# STRWL-S04-V00-Microcontroller.net
KiCad netlist of a schematic drawn in Altium Designer
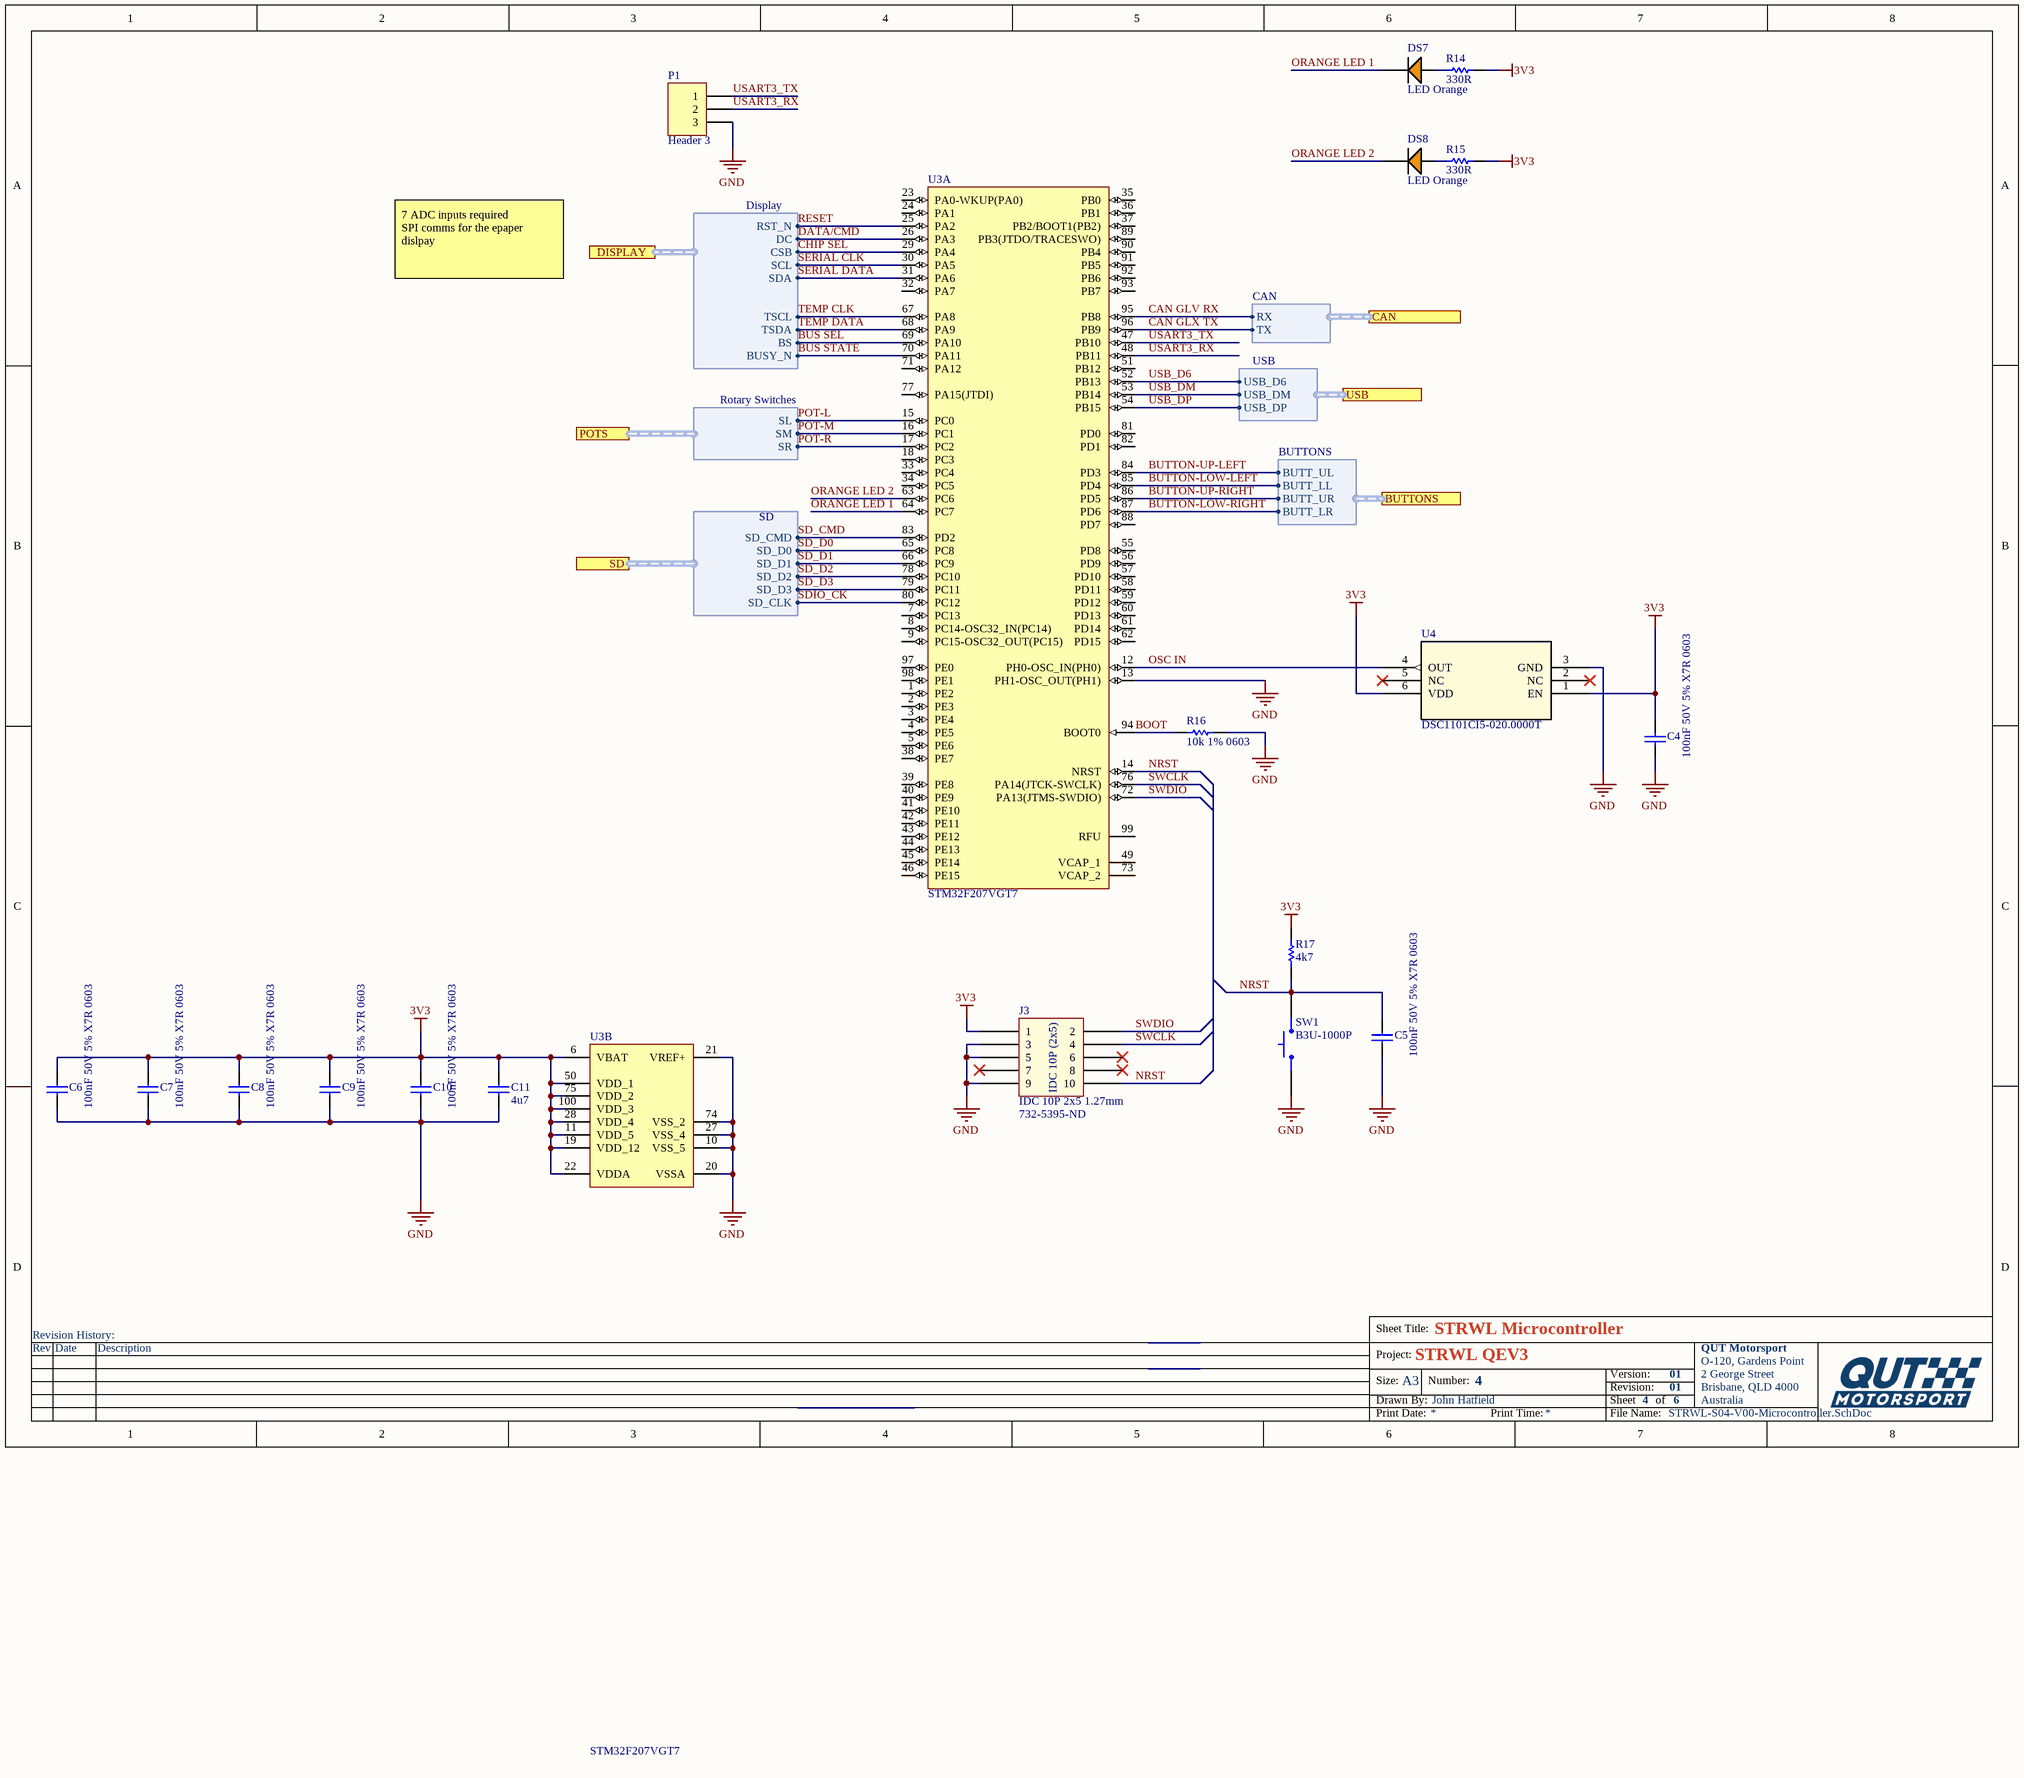
[diagram p0: STRWL-S04-V00-Microcontroller.SchDoc]

(export (version "E")
  (design (tool "Eeschema 10.0.6"))
  (components
    (comp (ref "C4")
      (value "100nF 50V 5% X7R 0603")
      (footprint "Cap_Ceramic_0603")
      (description "Capacitor, Ceramic, SMD, 100nF, 50V, 5%, X7R, 0603")
      (libsource (lib "StandardCapacitors") (part "100nF 50V 5% X7R 0603"))
    )
    (comp (ref "C5")
      (value "100nF 50V 5% X7R 0603")
      (footprint "Cap_Ceramic_0603")
      (description "Capacitor, Ceramic, SMD, 100nF, 50V, 5%, X7R, 0603")
      (libsource (lib "StandardCapacitors") (part "100nF 50V 5% X7R 0603"))
    )
    (comp (ref "C6")
      (value "100nF 50V 5% X7R 0603")
      (footprint "Cap_Ceramic_0603")
      (description "Capacitor, Ceramic, SMD, 100nF, 50V, 5%, X7R, 0603")
      (libsource (lib "StandardCapacitors") (part "100nF 50V 5% X7R 0603"))
    )
    (comp (ref "C7")
      (value "100nF 50V 5% X7R 0603")
      (footprint "Cap_Ceramic_0603")
      (description "Capacitor, Ceramic, SMD, 100nF, 50V, 5%, X7R, 0603")
      (libsource (lib "StandardCapacitors") (part "100nF 50V 5% X7R 0603"))
    )
    (comp (ref "C8")
      (value "100nF 50V 5% X7R 0603")
      (footprint "Cap_Ceramic_0603")
      (description "Capacitor, Ceramic, SMD, 100nF, 50V, 5%, X7R, 0603")
      (libsource (lib "StandardCapacitors") (part "100nF 50V 5% X7R 0603"))
    )
    (comp (ref "C9")
      (value "100nF 50V 5% X7R 0603")
      (footprint "Cap_Ceramic_0603")
      (description "Capacitor, Ceramic, SMD, 100nF, 50V, 5%, X7R, 0603")
      (libsource (lib "StandardCapacitors") (part "100nF 50V 5% X7R 0603"))
    )
    (comp (ref "C10")
      (value "100nF 50V 5% X7R 0603")
      (footprint "Cap_Ceramic_0603")
      (description "Capacitor, Ceramic, SMD, 100nF, 50V, 5%, X7R, 0603")
      (libsource (lib "StandardCapacitors") (part "100nF 50V 5% X7R 0603"))
    )
    (comp (ref "C11")
      (value "4u7")
      (footprint "Cap_Ceramic_0603")
      (description "Capacitor, Ceramic, SMD, 4u7, 50V, 5%, X7R, 0603")
      (libsource (lib "StandardCapacitors") (part "4u7 50V 5% X7R 0603"))
    )
    (comp (ref "DS7")
      (value "LED Orange")
      (footprint "LED ORANGE 0603")
      (libsource (lib "QUTMS_LEDLibrary") (part "LED ORANGE 0603"))
    )
    (comp (ref "DS8")
      (value "LED Orange")
      (footprint "LED ORANGE 0603")
      (libsource (lib "QUTMS_LEDLibrary") (part "LED ORANGE 0603"))
    )
    (comp (ref "J3")
      (value "IDC 10P 2x5 1.27mm")
      (footprint "IDC 1.27MM 10P")
      (libsource (lib "IDCConnectors") (part "IDC 10P 2x5 1.27mm"))
    )
    (comp (ref "P1")
      (value "Header 3")
      (footprint "HDR1X3")
      (description "Header, 3-Pin")
      (fields (field (name "PUBLISHER") "Altium Limited"))
      (libsource (lib "Miscellaneous Connectors") (part "Header 3"))
    )
    (comp (ref "R14")
      (value "330R")
      (footprint "Res_ThinFilm_0603")
      (description "Resistor, SMD, 330R, 0.1W, 5%, 0603")
      (libsource (lib "StandardResistors") (part "330R 5% 0603"))
    )
    (comp (ref "R15")
      (value "330R")
      (footprint "Res_ThinFilm_0603")
      (description "Resistor, SMD, 330R, 0.1W, 5%, 0603")
      (libsource (lib "StandardResistors") (part "330R 5% 0603"))
    )
    (comp (ref "R16")
      (value "10k 1% 0603")
      (footprint "Res_ThinFilm_0603")
      (description "Resistor, SMD, 20k, 0.1W, 5%, 0603")
      (libsource (lib "QUTMS-MCISOLibrary") (part "20k 1% 0603"))
    )
    (comp (ref "R17")
      (value "4k7")
      (footprint "Res_ThinFilm_0603")
      (description "Resistor, SMD, 4k7, 0.1W, 5%, 0603")
      (libsource (lib "StandardResistors") (part "4k7 5% 0603"))
    )
    (comp (ref "SW1")
      (value "B3U-1000P")
      (footprint "BTN B3U-1000P")
      (description "Omron B3U-1000P Ultra Miniture Switch")
      (libsource (lib "QUTMS_SwitchLibrary") (part "BTN B3U-1000P"))
    )
    (comp (ref "U3")
      (value "STM32F207VGT7")
      (footprint "STM-LQFP100_N")
      (libsource (lib "STM32F207VGT7") (part "STM32F207VGT7-Custom"))
    )
    (comp (ref "U4")
      (value "DSC1101CI5-020.0000T")
      (footprint "VDFN6_3P2X2P5_MCH")
      (description "No Description Available")
      (fields (field (name "COPYRIGHT") "Copyright (C) 2018 Accelerated Designs. All rights reserved"))
      (libsource (lib "DSC1101CI5-020.0000T") (part "DSC1101CI5-020.0000T"))
    )
  )
  (nets
    (net (code "8") (name "/BOOT") (class "Default")
      (node (ref "R16") (pin "1") (pinfunction "1_1") (pintype "passive"))
      (node (ref "U3") (pin "94") (pinfunction "BOOT0_94") (pintype "input"))
    )
    (net (code "9") (name "/BUS SEL") (class "Default")
      (node (ref "U3") (pin "69") (pinfunction "PA10_69") (pintype "bidirectional"))
    )
    (net (code "10") (name "/BUS STATE") (class "Default")
      (node (ref "U3") (pin "70") (pinfunction "PA11_70") (pintype "bidirectional"))
    )
    (net (code "11") (name "/BUTTON-LOW-LEFT") (class "Default")
      (node (ref "U3") (pin "85") (pinfunction "PD4_85") (pintype "bidirectional"))
    )
    (net (code "12") (name "/BUTTON-LOW-RIGHT") (class "Default")
      (node (ref "U3") (pin "87") (pinfunction "PD6_87") (pintype "bidirectional"))
    )
    (net (code "13") (name "/BUTTON-UP-LEFT") (class "Default")
      (node (ref "U3") (pin "84") (pinfunction "PD3_84") (pintype "bidirectional"))
    )
    (net (code "14") (name "/BUTTON-UP-RIGHT") (class "Default")
      (node (ref "U3") (pin "86") (pinfunction "PD5_86") (pintype "bidirectional"))
    )
    (net (code "15") (name "/CAN GLV RX") (class "Default")
      (node (ref "U3") (pin "95") (pinfunction "PB8_95") (pintype "bidirectional"))
    )
    (net (code "16") (name "/CAN GLX TX") (class "Default")
      (node (ref "U3") (pin "96") (pinfunction "PB9_96") (pintype "bidirectional"))
    )
    (net (code "17") (name "/CHIP SEL") (class "Default")
      (node (ref "U3") (pin "29") (pinfunction "PA4_29") (pintype "bidirectional"))
    )
    (net (code "18") (name "/DATA{slash}CMD") (class "Default")
      (node (ref "U3") (pin "26") (pinfunction "PA3_26") (pintype "bidirectional"))
    )
    (net (code "19") (name "/NRST") (class "Default")
      (node (ref "C5") (pin "2") (pinfunction "2_2") (pintype "passive"))
      (node (ref "J3") (pin "10") (pinfunction "10_10") (pintype "passive"))
      (node (ref "R17") (pin "1") (pinfunction "1_1") (pintype "passive"))
      (node (ref "SW1") (pin "2") (pinfunction "2_2") (pintype "passive"))
      (node (ref "U3") (pin "14") (pinfunction "NRST_14") (pintype "bidirectional"))
    )
    (net (code "20") (name "/ORANGE LED 1") (class "Default")
      (node (ref "DS7") (pin "2") (pinfunction "C_2") (pintype "passive"))
      (node (ref "U3") (pin "64") (pinfunction "PC7_64") (pintype "bidirectional"))
    )
    (net (code "21") (name "/ORANGE LED 2") (class "Default")
      (node (ref "DS8") (pin "2") (pinfunction "C_2") (pintype "passive"))
      (node (ref "U3") (pin "63") (pinfunction "PC6_63") (pintype "bidirectional"))
    )
    (net (code "22") (name "/OSC IN") (class "Default")
      (node (ref "U3") (pin "12") (pinfunction "PH0-OSC_IN(PH0)_12") (pintype "bidirectional"))
      (node (ref "U4") (pin "4") (pinfunction "OUT_4") (pintype "output"))
    )
    (net (code "23") (name "/POT-L") (class "Default")
      (node (ref "U3") (pin "15") (pinfunction "PC0_15") (pintype "bidirectional"))
    )
    (net (code "24") (name "/POT-M") (class "Default")
      (node (ref "U3") (pin "16") (pinfunction "PC1_16") (pintype "bidirectional"))
    )
    (net (code "25") (name "/POT-R") (class "Default")
      (node (ref "U3") (pin "17") (pinfunction "PC2_17") (pintype "bidirectional"))
    )
    (net (code "26") (name "/RESET") (class "Default")
      (node (ref "U3") (pin "25") (pinfunction "PA2_25") (pintype "bidirectional"))
    )
    (net (code "27") (name "/SDIO_CK") (class "Default")
      (node (ref "U3") (pin "80") (pinfunction "PC12_80") (pintype "bidirectional"))
    )
    (net (code "28") (name "/SD_CMD") (class "Default")
      (node (ref "U3") (pin "83") (pinfunction "PD2_83") (pintype "bidirectional"))
    )
    (net (code "29") (name "/SD_D0") (class "Default")
      (node (ref "U3") (pin "65") (pinfunction "PC8_65") (pintype "bidirectional"))
    )
    (net (code "30") (name "/SD_D1") (class "Default")
      (node (ref "U3") (pin "66") (pinfunction "PC9_66") (pintype "bidirectional"))
    )
    (net (code "31") (name "/SD_D2") (class "Default")
      (node (ref "U3") (pin "78") (pinfunction "PC10_78") (pintype "bidirectional"))
    )
    (net (code "32") (name "/SD_D3") (class "Default")
      (node (ref "U3") (pin "79") (pinfunction "PC11_79") (pintype "bidirectional"))
    )
    (net (code "33") (name "/SERIAL CLK") (class "Default")
      (node (ref "U3") (pin "30") (pinfunction "PA5_30") (pintype "bidirectional"))
    )
    (net (code "34") (name "/SERIAL DATA") (class "Default")
      (node (ref "U3") (pin "31") (pinfunction "PA6_31") (pintype "bidirectional"))
    )
    (net (code "35") (name "/SWCLK") (class "Default")
      (node (ref "J3") (pin "4") (pinfunction "4_4") (pintype "passive"))
      (node (ref "U3") (pin "76") (pinfunction "PA14(JTCK-SWCLK)_76") (pintype "bidirectional"))
    )
    (net (code "36") (name "/SWDIO") (class "Default")
      (node (ref "J3") (pin "2") (pinfunction "2_2") (pintype "passive"))
      (node (ref "U3") (pin "72") (pinfunction "PA13(JTMS-SWDIO)_72") (pintype "bidirectional"))
    )
    (net (code "37") (name "/TEMP CLK") (class "Default")
      (node (ref "U3") (pin "67") (pinfunction "PA8_67") (pintype "bidirectional"))
    )
    (net (code "38") (name "/TEMP DATA") (class "Default")
      (node (ref "U3") (pin "68") (pinfunction "PA9_68") (pintype "bidirectional"))
    )
    (net (code "39") (name "/USART3_RX") (class "Default")
      (node (ref "P1") (pin "2") (pinfunction "2_2") (pintype "passive"))
      (node (ref "U3") (pin "48") (pinfunction "PB11_48") (pintype "bidirectional"))
    )
    (net (code "40") (name "/USART3_TX") (class "Default")
      (node (ref "P1") (pin "1") (pinfunction "1_1") (pintype "passive"))
      (node (ref "U3") (pin "47") (pinfunction "PB10_47") (pintype "bidirectional"))
    )
    (net (code "41") (name "/USB_D6") (class "Default")
      (node (ref "U3") (pin "52") (pinfunction "PB13_52") (pintype "bidirectional"))
    )
    (net (code "42") (name "/USB_DM") (class "Default")
      (node (ref "U3") (pin "53") (pinfunction "PB14_53") (pintype "bidirectional"))
    )
    (net (code "43") (name "/USB_DP") (class "Default")
      (node (ref "U3") (pin "54") (pinfunction "PB15_54") (pintype "bidirectional"))
    )
    (net (code "50") (name "3V3") (class "Default")
      (node (ref "C10") (pin "2") (pinfunction "2_2") (pintype "passive"))
      (node (ref "C11") (pin "2") (pinfunction "2_2") (pintype "passive"))
      (node (ref "C4") (pin "2") (pinfunction "2_2") (pintype "passive"))
      (node (ref "C6") (pin "2") (pinfunction "2_2") (pintype "passive"))
      (node (ref "C7") (pin "2") (pinfunction "2_2") (pintype "passive"))
      (node (ref "C8") (pin "2") (pinfunction "2_2") (pintype "passive"))
      (node (ref "C9") (pin "2") (pinfunction "2_2") (pintype "passive"))
      (node (ref "J3") (pin "1") (pinfunction "1_1") (pintype "passive"))
      (node (ref "R14") (pin "2") (pinfunction "2_2") (pintype "passive"))
      (node (ref "R15") (pin "2") (pinfunction "2_2") (pintype "passive"))
      (node (ref "R17") (pin "2") (pinfunction "2_2") (pintype "passive"))
      (node (ref "U3") (pin "100") (pinfunction "VDD_3_100") (pintype "power_in"))
      (node (ref "U3") (pin "11") (pinfunction "VDD_5_11") (pintype "power_in"))
      (node (ref "U3") (pin "19") (pinfunction "VDD_12_19") (pintype "power_in"))
      (node (ref "U3") (pin "22") (pinfunction "VDDA_22") (pintype "power_in"))
      (node (ref "U3") (pin "28") (pinfunction "VDD_4_28") (pintype "power_in"))
      (node (ref "U3") (pin "50") (pinfunction "VDD_1_50") (pintype "power_in"))
      (node (ref "U3") (pin "6") (pinfunction "VBAT_6") (pintype "power_in"))
      (node (ref "U3") (pin "75") (pinfunction "VDD_2_75") (pintype "power_in"))
      (node (ref "U4") (pin "1") (pinfunction "EN_1") (pintype "passive"))
      (node (ref "U4") (pin "6") (pinfunction "VDD_6") (pintype "power_in"))
    )
    (net (code "51") (name "GND") (class "Default")
      (node (ref "C10") (pin "1") (pinfunction "1_1") (pintype "passive"))
      (node (ref "C11") (pin "1") (pinfunction "1_1") (pintype "passive"))
      (node (ref "C4") (pin "1") (pinfunction "1_1") (pintype "passive"))
      (node (ref "C5") (pin "1") (pinfunction "1_1") (pintype "passive"))
      (node (ref "C6") (pin "1") (pinfunction "1_1") (pintype "passive"))
      (node (ref "C7") (pin "1") (pinfunction "1_1") (pintype "passive"))
      (node (ref "C8") (pin "1") (pinfunction "1_1") (pintype "passive"))
      (node (ref "C9") (pin "1") (pinfunction "1_1") (pintype "passive"))
      (node (ref "J3") (pin "3") (pinfunction "3_3") (pintype "passive"))
      (node (ref "J3") (pin "5") (pinfunction "5_5") (pintype "passive"))
      (node (ref "J3") (pin "9") (pinfunction "9_9") (pintype "passive"))
      (node (ref "P1") (pin "3") (pinfunction "3_3") (pintype "passive"))
      (node (ref "R16") (pin "2") (pinfunction "2_2") (pintype "passive"))
      (node (ref "SW1") (pin "1") (pinfunction "1_1") (pintype "passive"))
      (node (ref "U3") (pin "10") (pinfunction "VSS_5_10") (pintype "power_in"))
      (node (ref "U3") (pin "13") (pinfunction "PH1-OSC_OUT(PH1)_13") (pintype "bidirectional"))
      (node (ref "U3") (pin "20") (pinfunction "VSSA_20") (pintype "power_in"))
      (node (ref "U3") (pin "21") (pinfunction "VREF+_21") (pintype "power_in"))
      (node (ref "U3") (pin "27") (pinfunction "VSS_4_27") (pintype "power_in"))
      (node (ref "U3") (pin "74") (pinfunction "VSS_2_74") (pintype "power_in"))
      (node (ref "U4") (pin "3") (pinfunction "GND_3") (pintype "passive"))
    )
    (net (code "52") (name "Net-(DS7-A)") (class "Default")
      (node (ref "DS7") (pin "1") (pinfunction "A_1") (pintype "passive"))
      (node (ref "R14") (pin "1") (pinfunction "1_1") (pintype "passive"))
    )
    (net (code "53") (name "Net-(DS8-A)") (class "Default")
      (node (ref "DS8") (pin "1") (pinfunction "A_1") (pintype "passive"))
      (node (ref "R15") (pin "1") (pinfunction "1_1") (pintype "passive"))
    )
    (net (code "54") (name "unconnected-(J3-Pad6)") (class "Default")
      (node (ref "J3") (pin "6") (pinfunction "6_6") (pintype "passive+no_connect"))
    )
    (net (code "55") (name "unconnected-(J3-Pad7)") (class "Default")
      (node (ref "J3") (pin "7") (pinfunction "7_7") (pintype "passive+no_connect"))
    )
    (net (code "56") (name "unconnected-(J3-Pad8)") (class "Default")
      (node (ref "J3") (pin "8") (pinfunction "8_8") (pintype "passive+no_connect"))
    )
    (net (code "57") (name "unconnected-(U3A-PA0-WKUP(PA0)-Pad23)") (class "Default")
      (node (ref "U3") (pin "23") (pinfunction "PA0-WKUP(PA0)_23") (pintype "bidirectional"))
    )
    (net (code "58") (name "unconnected-(U3A-PA1-Pad24)") (class "Default")
      (node (ref "U3") (pin "24") (pinfunction "PA1_24") (pintype "bidirectional"))
    )
    (net (code "59") (name "unconnected-(U3A-PA7-Pad32)") (class "Default")
      (node (ref "U3") (pin "32") (pinfunction "PA7_32") (pintype "bidirectional"))
    )
    (net (code "60") (name "unconnected-(U3A-PA12-Pad71)") (class "Default")
      (node (ref "U3") (pin "71") (pinfunction "PA12_71") (pintype "bidirectional"))
    )
    (net (code "61") (name "unconnected-(U3A-PA15(JTDI)-Pad77)") (class "Default")
      (node (ref "U3") (pin "77") (pinfunction "PA15(JTDI)_77") (pintype "bidirectional"))
    )
    (net (code "62") (name "unconnected-(U3A-PB0-Pad35)") (class "Default")
      (node (ref "U3") (pin "35") (pinfunction "PB0_35") (pintype "bidirectional"))
    )
    (net (code "63") (name "unconnected-(U3A-PB1-Pad36)") (class "Default")
      (node (ref "U3") (pin "36") (pinfunction "PB1_36") (pintype "bidirectional"))
    )
    (net (code "64") (name "unconnected-(U3A-PB2{slash}BOOT1(PB2)-Pad37)") (class "Default")
      (node (ref "U3") (pin "37") (pinfunction "PB2/BOOT1(PB2)_37") (pintype "bidirectional"))
    )
    (net (code "65") (name "unconnected-(U3A-PB3(JTDO{slash}TRACESWO)-Pad89)") (class "Default")
      (node (ref "U3") (pin "89") (pinfunction "PB3(JTDO/TRACESWO)_89") (pintype "bidirectional"))
    )
    (net (code "66") (name "unconnected-(U3A-PB4-Pad90)") (class "Default")
      (node (ref "U3") (pin "90") (pinfunction "PB4_90") (pintype "bidirectional"))
    )
    (net (code "67") (name "unconnected-(U3A-PB5-Pad91)") (class "Default")
      (node (ref "U3") (pin "91") (pinfunction "PB5_91") (pintype "bidirectional"))
    )
    (net (code "68") (name "unconnected-(U3A-PB6-Pad92)") (class "Default")
      (node (ref "U3") (pin "92") (pinfunction "PB6_92") (pintype "bidirectional"))
    )
    (net (code "69") (name "unconnected-(U3A-PB7-Pad93)") (class "Default")
      (node (ref "U3") (pin "93") (pinfunction "PB7_93") (pintype "bidirectional"))
    )
    (net (code "70") (name "unconnected-(U3A-PB12-Pad51)") (class "Default")
      (node (ref "U3") (pin "51") (pinfunction "PB12_51") (pintype "bidirectional"))
    )
    (net (code "71") (name "unconnected-(U3A-PC3-Pad18)") (class "Default")
      (node (ref "U3") (pin "18") (pinfunction "PC3_18") (pintype "bidirectional"))
    )
    (net (code "72") (name "unconnected-(U3A-PC4-Pad33)") (class "Default")
      (node (ref "U3") (pin "33") (pinfunction "PC4_33") (pintype "bidirectional"))
    )
    (net (code "73") (name "unconnected-(U3A-PC5-Pad34)") (class "Default")
      (node (ref "U3") (pin "34") (pinfunction "PC5_34") (pintype "bidirectional"))
    )
    (net (code "74") (name "unconnected-(U3A-PC13-Pad7)") (class "Default")
      (node (ref "U3") (pin "7") (pinfunction "PC13_7") (pintype "bidirectional"))
    )
    (net (code "75") (name "unconnected-(U3A-PC14-OSC32_IN(PC14)-Pad8)") (class "Default")
      (node (ref "U3") (pin "8") (pinfunction "PC14-OSC32_IN(PC14)_8") (pintype "bidirectional"))
    )
    (net (code "76") (name "unconnected-(U3A-PC15-OSC32_OUT(PC15)-Pad9)") (class "Default")
      (node (ref "U3") (pin "9") (pinfunction "PC15-OSC32_OUT(PC15)_9") (pintype "bidirectional"))
    )
    (net (code "77") (name "unconnected-(U3A-PD0-Pad81)") (class "Default")
      (node (ref "U3") (pin "81") (pinfunction "PD0_81") (pintype "bidirectional"))
    )
    (net (code "78") (name "unconnected-(U3A-PD1-Pad82)") (class "Default")
      (node (ref "U3") (pin "82") (pinfunction "PD1_82") (pintype "bidirectional"))
    )
    (net (code "79") (name "unconnected-(U3A-PD7-Pad88)") (class "Default")
      (node (ref "U3") (pin "88") (pinfunction "PD7_88") (pintype "bidirectional"))
    )
    (net (code "80") (name "unconnected-(U3A-PD8-Pad55)") (class "Default")
      (node (ref "U3") (pin "55") (pinfunction "PD8_55") (pintype "bidirectional"))
    )
    (net (code "81") (name "unconnected-(U3A-PD9-Pad56)") (class "Default")
      (node (ref "U3") (pin "56") (pinfunction "PD9_56") (pintype "bidirectional"))
    )
    (net (code "82") (name "unconnected-(U3A-PD10-Pad57)") (class "Default")
      (node (ref "U3") (pin "57") (pinfunction "PD10_57") (pintype "bidirectional"))
    )
    (net (code "83") (name "unconnected-(U3A-PD11-Pad58)") (class "Default")
      (node (ref "U3") (pin "58") (pinfunction "PD11_58") (pintype "bidirectional"))
    )
    (net (code "84") (name "unconnected-(U3A-PD12-Pad59)") (class "Default")
      (node (ref "U3") (pin "59") (pinfunction "PD12_59") (pintype "bidirectional"))
    )
    (net (code "85") (name "unconnected-(U3A-PD13-Pad60)") (class "Default")
      (node (ref "U3") (pin "60") (pinfunction "PD13_60") (pintype "bidirectional"))
    )
    (net (code "86") (name "unconnected-(U3A-PD14-Pad61)") (class "Default")
      (node (ref "U3") (pin "61") (pinfunction "PD14_61") (pintype "bidirectional"))
    )
    (net (code "87") (name "unconnected-(U3A-PD15-Pad62)") (class "Default")
      (node (ref "U3") (pin "62") (pinfunction "PD15_62") (pintype "bidirectional"))
    )
    (net (code "88") (name "unconnected-(U3A-PE0-Pad97)") (class "Default")
      (node (ref "U3") (pin "97") (pinfunction "PE0_97") (pintype "bidirectional"))
    )
    (net (code "89") (name "unconnected-(U3A-PE1-Pad98)") (class "Default")
      (node (ref "U3") (pin "98") (pinfunction "PE1_98") (pintype "bidirectional"))
    )
    (net (code "90") (name "unconnected-(U3A-PE2-Pad1)") (class "Default")
      (node (ref "U3") (pin "1") (pinfunction "PE2_1") (pintype "bidirectional"))
    )
    (net (code "91") (name "unconnected-(U3A-PE3-Pad2)") (class "Default")
      (node (ref "U3") (pin "2") (pinfunction "PE3_2") (pintype "bidirectional"))
    )
    (net (code "92") (name "unconnected-(U3A-PE4-Pad3)") (class "Default")
      (node (ref "U3") (pin "3") (pinfunction "PE4_3") (pintype "bidirectional"))
    )
    (net (code "93") (name "unconnected-(U3A-PE5-Pad4)") (class "Default")
      (node (ref "U3") (pin "4") (pinfunction "PE5_4") (pintype "bidirectional"))
    )
    (net (code "94") (name "unconnected-(U3A-PE6-Pad5)") (class "Default")
      (node (ref "U3") (pin "5") (pinfunction "PE6_5") (pintype "bidirectional"))
    )
    (net (code "95") (name "unconnected-(U3A-PE7-Pad38)") (class "Default")
      (node (ref "U3") (pin "38") (pinfunction "PE7_38") (pintype "bidirectional"))
    )
    (net (code "96") (name "unconnected-(U3A-PE8-Pad39)") (class "Default")
      (node (ref "U3") (pin "39") (pinfunction "PE8_39") (pintype "bidirectional"))
    )
    (net (code "97") (name "unconnected-(U3A-PE9-Pad40)") (class "Default")
      (node (ref "U3") (pin "40") (pinfunction "PE9_40") (pintype "bidirectional"))
    )
    (net (code "98") (name "unconnected-(U3A-PE10-Pad41)") (class "Default")
      (node (ref "U3") (pin "41") (pinfunction "PE10_41") (pintype "bidirectional"))
    )
    (net (code "99") (name "unconnected-(U3A-PE11-Pad42)") (class "Default")
      (node (ref "U3") (pin "42") (pinfunction "PE11_42") (pintype "bidirectional"))
    )
    (net (code "100") (name "unconnected-(U3A-PE12-Pad43)") (class "Default")
      (node (ref "U3") (pin "43") (pinfunction "PE12_43") (pintype "bidirectional"))
    )
    (net (code "101") (name "unconnected-(U3A-PE13-Pad44)") (class "Default")
      (node (ref "U3") (pin "44") (pinfunction "PE13_44") (pintype "bidirectional"))
    )
    (net (code "102") (name "unconnected-(U3A-PE14-Pad45)") (class "Default")
      (node (ref "U3") (pin "45") (pinfunction "PE14_45") (pintype "bidirectional"))
    )
    (net (code "103") (name "unconnected-(U3A-PE15-Pad46)") (class "Default")
      (node (ref "U3") (pin "46") (pinfunction "PE15_46") (pintype "bidirectional"))
    )
    (net (code "104") (name "unconnected-(U3A-RFU-Pad99)") (class "Default")
      (node (ref "U3") (pin "99") (pinfunction "RFU_99") (pintype "passive"))
    )
    (net (code "105") (name "unconnected-(U3A-VCAP_1-Pad49)") (class "Default")
      (node (ref "U3") (pin "49") (pinfunction "VCAP_1_49") (pintype "power_in"))
    )
    (net (code "106") (name "unconnected-(U3A-VCAP_2-Pad73)") (class "Default")
      (node (ref "U3") (pin "73") (pinfunction "VCAP_2_73") (pintype "power_in"))
    )
    (net (code "107") (name "unconnected-(U4-NC-Pad2)") (class "Default")
      (node (ref "U4") (pin "2") (pinfunction "NC_2") (pintype "passive+no_connect"))
    )
    (net (code "108") (name "unconnected-(U4-NC-Pad5)") (class "Default")
      (node (ref "U4") (pin "5") (pinfunction "NC_5") (pintype "passive+no_connect"))
    )
  )
)
